# WifiGarage.net
KiCad netlist of a schematic drawn in EAGLE
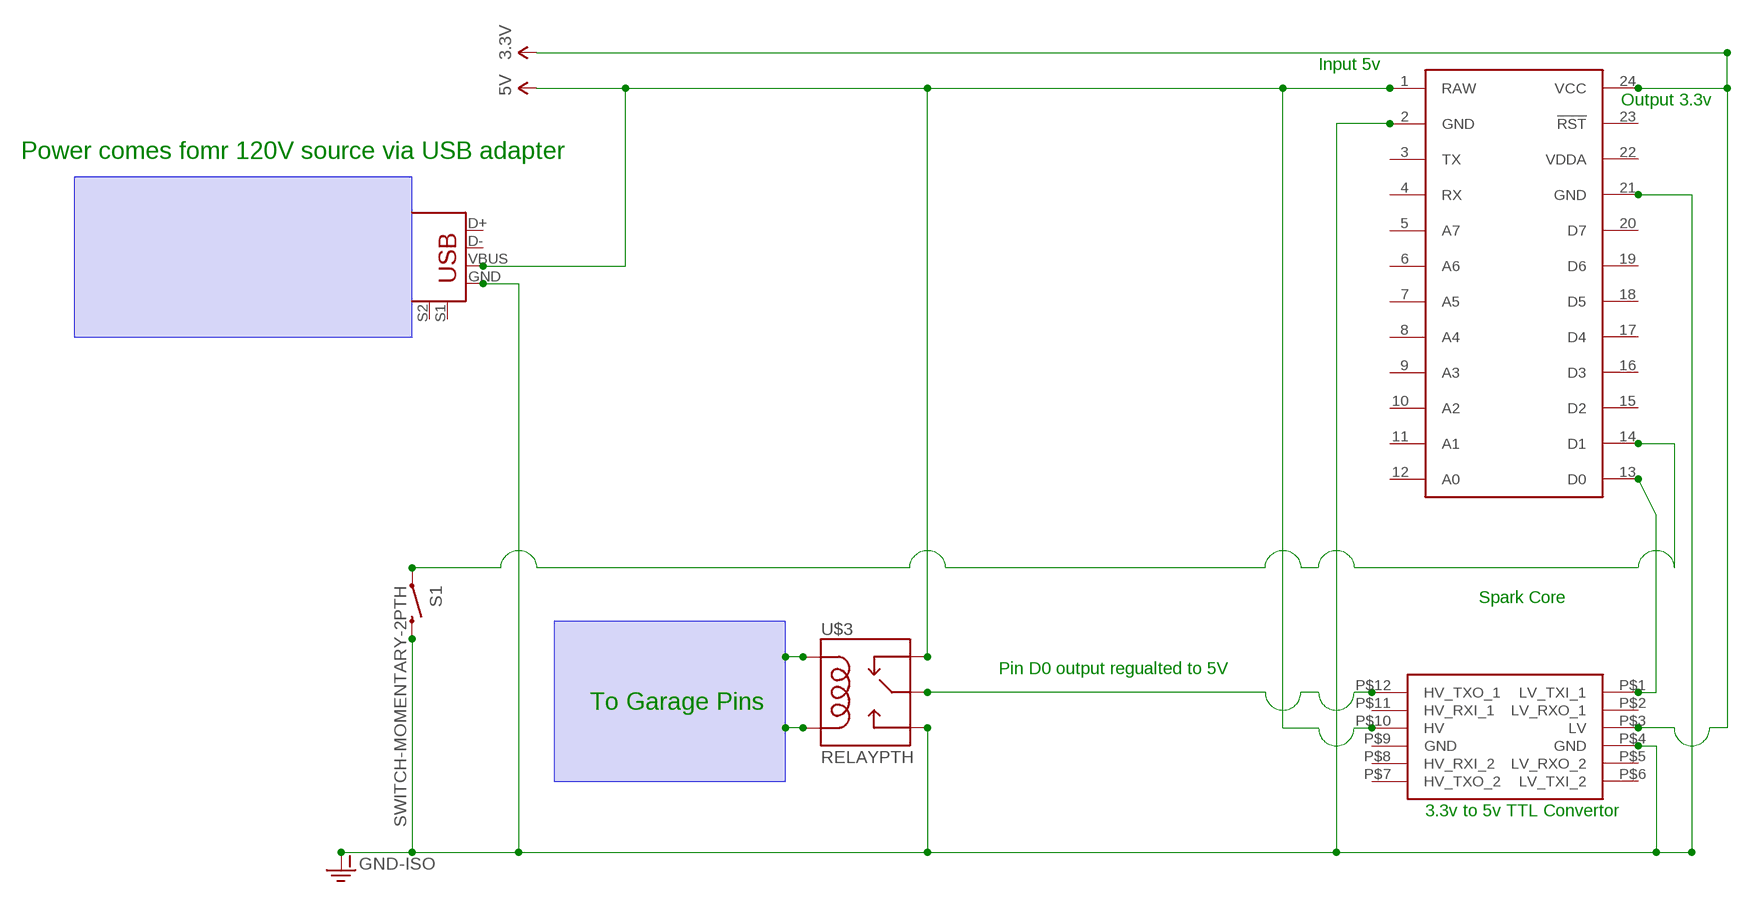
[diagram p0: schematic, sheet 1]

(export (version "E")
  (design (tool "Eeschema 10.0.6"))
  (components
    (comp (ref "S1")
      (value "SWITCH-MOMENTARY-2PTH")
      (footprint "eagle-import:TACTILE-PTH")
      (libsource (lib "eagle-import") (part "SWITCH-MOMENTARY-2PTH"))
    )
    (comp (ref "U$1")
      (value "SPARK_CORECORE")
      (footprint "eagle-import:SPARK_CORE")
      (libsource (lib "eagle-import") (part "SPARK_CORECORE"))
    )
    (comp (ref "U$2")
      (value "LOGIC_LEVEL_CONVERTER")
      (footprint "eagle-import:LOGIC_LEVEL_CONVERTER")
      (libsource (lib "eagle-import") (part "LOGIC_LEVEL_CONVERTER"))
    )
    (comp (ref "U$3")
      (value "RELAYPTH")
      (footprint "eagle-import:RELAY-G5Q")
      (libsource (lib "eagle-import") (part "RELAYPTH"))
    )
    (comp (ref "U$4")
      (value "USB+SHIELD")
      (footprint "eagle-import:USB-B-PTH")
      (libsource (lib "eagle-import") (part "USB+SHIELD"))
    )
  )
  (nets
    (net (code "1") (name "/VDDA") (class "Default")
      (node (ref "U$1") (pin "22") (pinfunction "VDDA_22") (pintype "power_in"))
    )
    (net (code "2") (name "3.3V") (class "Default")
      (node (ref "U$1") (pin "24") (pinfunction "VCC_24") (pintype "power_in"))
      (node (ref "U$2") (pin "P$3") (pinfunction "LV_P$3") (pintype "bidirectional"))
    )
    (net (code "3") (name "5V") (class "Default")
      (node (ref "U$1") (pin "1") (pinfunction "RAW_1") (pintype "power_in"))
      (node (ref "U$2") (pin "P$10") (pinfunction "HV_P$10") (pintype "bidirectional"))
      (node (ref "U$3") (pin "4") (pinfunction "NC_4") (pintype "bidirectional"))
      (node (ref "U$4") (pin "VBUS") (pinfunction "VBUS_VBUS") (pintype "bidirectional"))
    )
    (net (code "4") (name "GND-ISO") (class "Default")
      (node (ref "S1") (pin "3") (pinfunction "2_3") (pintype "passive"))
      (node (ref "U$1") (pin "2") (pinfunction "GND_2") (pintype "power_in"))
      (node (ref "U$1") (pin "21") (pinfunction "GND_21") (pintype "power_in"))
      (node (ref "U$2") (pin "P$4") (pinfunction "GND_P$4") (pintype "bidirectional"))
      (node (ref "U$3") (pin "3") (pinfunction "NO_3") (pintype "bidirectional"))
      (node (ref "U$4") (pin "GND") (pinfunction "GND_GND") (pintype "bidirectional"))
    )
    (net (code "5") (name "Net-(U$1-D0)") (class "Default")
      (node (ref "U$1") (pin "13") (pinfunction "D0_13") (pintype "bidirectional"))
      (node (ref "U$2") (pin "P$1") (pinfunction "LV_TXI_1_P$1") (pintype "bidirectional"))
    )
    (net (code "6") (name "Net-(U$1-D1)") (class "Default")
      (node (ref "S1") (pin "1") (pinfunction "1_1") (pintype "passive"))
      (node (ref "U$1") (pin "14") (pinfunction "D1_14") (pintype "bidirectional"))
    )
    (net (code "7") (name "Net-(U$2-HV_TXO_1)") (class "Default")
      (node (ref "U$2") (pin "P$12") (pinfunction "HV_TXO_1_P$12") (pintype "bidirectional"))
      (node (ref "U$3") (pin "2") (pinfunction "MAIN_2") (pintype "bidirectional"))
    )
    (net (code "8") (name "unconnected-(U$1-A0-Pad12)") (class "Default")
      (node (ref "U$1") (pin "12") (pinfunction "A0_12") (pintype "bidirectional"))
    )
    (net (code "9") (name "unconnected-(U$1-A1-Pad11)") (class "Default")
      (node (ref "U$1") (pin "11") (pinfunction "A1_11") (pintype "bidirectional"))
    )
    (net (code "10") (name "unconnected-(U$1-A2-Pad10)") (class "Default")
      (node (ref "U$1") (pin "10") (pinfunction "A2_10") (pintype "bidirectional"))
    )
    (net (code "11") (name "unconnected-(U$1-A3-Pad9)") (class "Default")
      (node (ref "U$1") (pin "9") (pinfunction "A3_9") (pintype "bidirectional"))
    )
    (net (code "12") (name "unconnected-(U$1-A4-Pad8)") (class "Default")
      (node (ref "U$1") (pin "8") (pinfunction "A4_8") (pintype "bidirectional"))
    )
    (net (code "13") (name "unconnected-(U$1-A5-Pad7)") (class "Default")
      (node (ref "U$1") (pin "7") (pinfunction "A5_7") (pintype "bidirectional"))
    )
    (net (code "14") (name "unconnected-(U$1-A6-Pad6)") (class "Default")
      (node (ref "U$1") (pin "6") (pinfunction "A6_6") (pintype "bidirectional"))
    )
    (net (code "15") (name "unconnected-(U$1-A7-Pad5)") (class "Default")
      (node (ref "U$1") (pin "5") (pinfunction "A7_5") (pintype "bidirectional"))
    )
    (net (code "16") (name "unconnected-(U$1-D2-Pad15)") (class "Default")
      (node (ref "U$1") (pin "15") (pinfunction "D2_15") (pintype "bidirectional"))
    )
    (net (code "17") (name "unconnected-(U$1-D3-Pad16)") (class "Default")
      (node (ref "U$1") (pin "16") (pinfunction "D3_16") (pintype "bidirectional"))
    )
    (net (code "18") (name "unconnected-(U$1-D4-Pad17)") (class "Default")
      (node (ref "U$1") (pin "17") (pinfunction "D4_17") (pintype "bidirectional"))
    )
    (net (code "19") (name "unconnected-(U$1-D5-Pad18)") (class "Default")
      (node (ref "U$1") (pin "18") (pinfunction "D5_18") (pintype "bidirectional"))
    )
    (net (code "20") (name "unconnected-(U$1-D6-Pad19)") (class "Default")
      (node (ref "U$1") (pin "19") (pinfunction "D6_19") (pintype "bidirectional"))
    )
    (net (code "21") (name "unconnected-(U$1-D7-Pad20)") (class "Default")
      (node (ref "U$1") (pin "20") (pinfunction "D7_20") (pintype "bidirectional"))
    )
    (net (code "22") (name "unconnected-(U$1-RX-Pad4)") (class "Default")
      (node (ref "U$1") (pin "4") (pinfunction "RX_4") (pintype "bidirectional"))
    )
    (net (code "23") (name "unconnected-(U$1-TX-Pad3)") (class "Default")
      (node (ref "U$1") (pin "3") (pinfunction "TX_3") (pintype "bidirectional"))
    )
    (net (code "24") (name "unconnected-(U$1-~{RST}-Pad23)") (class "Default")
      (node (ref "U$1") (pin "23") (pinfunction "~{RST}_23") (pintype "bidirectional"))
    )
    (net (code "25") (name "unconnected-(U$2-GND-PadP$9)") (class "Default")
      (node (ref "U$2") (pin "P$9") (pinfunction "GND_P$9") (pintype "bidirectional"))
    )
    (net (code "26") (name "unconnected-(U$2-HV_RXI_1-PadP$11)") (class "Default")
      (node (ref "U$2") (pin "P$11") (pinfunction "HV_RXI_1_P$11") (pintype "bidirectional"))
    )
    (net (code "27") (name "unconnected-(U$2-HV_RXI_2-PadP$8)") (class "Default")
      (node (ref "U$2") (pin "P$8") (pinfunction "HV_RXI_2_P$8") (pintype "bidirectional"))
    )
    (net (code "28") (name "unconnected-(U$2-HV_TXO_2-PadP$7)") (class "Default")
      (node (ref "U$2") (pin "P$7") (pinfunction "HV_TXO_2_P$7") (pintype "bidirectional"))
    )
    (net (code "29") (name "unconnected-(U$2-LV_RXO_1-PadP$2)") (class "Default")
      (node (ref "U$2") (pin "P$2") (pinfunction "LV_RXO_1_P$2") (pintype "bidirectional"))
    )
    (net (code "30") (name "unconnected-(U$2-LV_RXO_2-PadP$5)") (class "Default")
      (node (ref "U$2") (pin "P$5") (pinfunction "LV_RXO_2_P$5") (pintype "bidirectional"))
    )
    (net (code "31") (name "unconnected-(U$2-LV_TXI_2-PadP$6)") (class "Default")
      (node (ref "U$2") (pin "P$6") (pinfunction "LV_TXI_2_P$6") (pintype "bidirectional"))
    )
    (net (code "32") (name "unconnected-(U$3-COIL1-Pad5)") (class "Default")
      (node (ref "U$3") (pin "5") (pinfunction "COIL1_5") (pintype "bidirectional"))
    )
    (net (code "33") (name "unconnected-(U$3-COIL2-Pad1)") (class "Default")
      (node (ref "U$3") (pin "1") (pinfunction "COIL2_1") (pintype "bidirectional"))
    )
    (net (code "34") (name "unconnected-(U$4-PadD+)") (class "Default")
      (node (ref "U$4") (pin "D+") (pinfunction "D+_D+") (pintype "bidirectional"))
    )
    (net (code "35") (name "unconnected-(U$4-PadD-)") (class "Default")
      (node (ref "U$4") (pin "D-") (pinfunction "D-_D-") (pintype "bidirectional"))
    )
    (net (code "36") (name "unconnected-(U$4-PadS1)") (class "Default")
      (node (ref "U$4") (pin "S1") (pinfunction "S1_S1") (pintype "bidirectional"))
    )
    (net (code "37") (name "unconnected-(U$4-PadS2)") (class "Default")
      (node (ref "U$4") (pin "S2") (pinfunction "S2_S2") (pintype "bidirectional"))
    )
  )
)
